# 2.net
KiCad netlist of a schematic drawn in EasyEDA
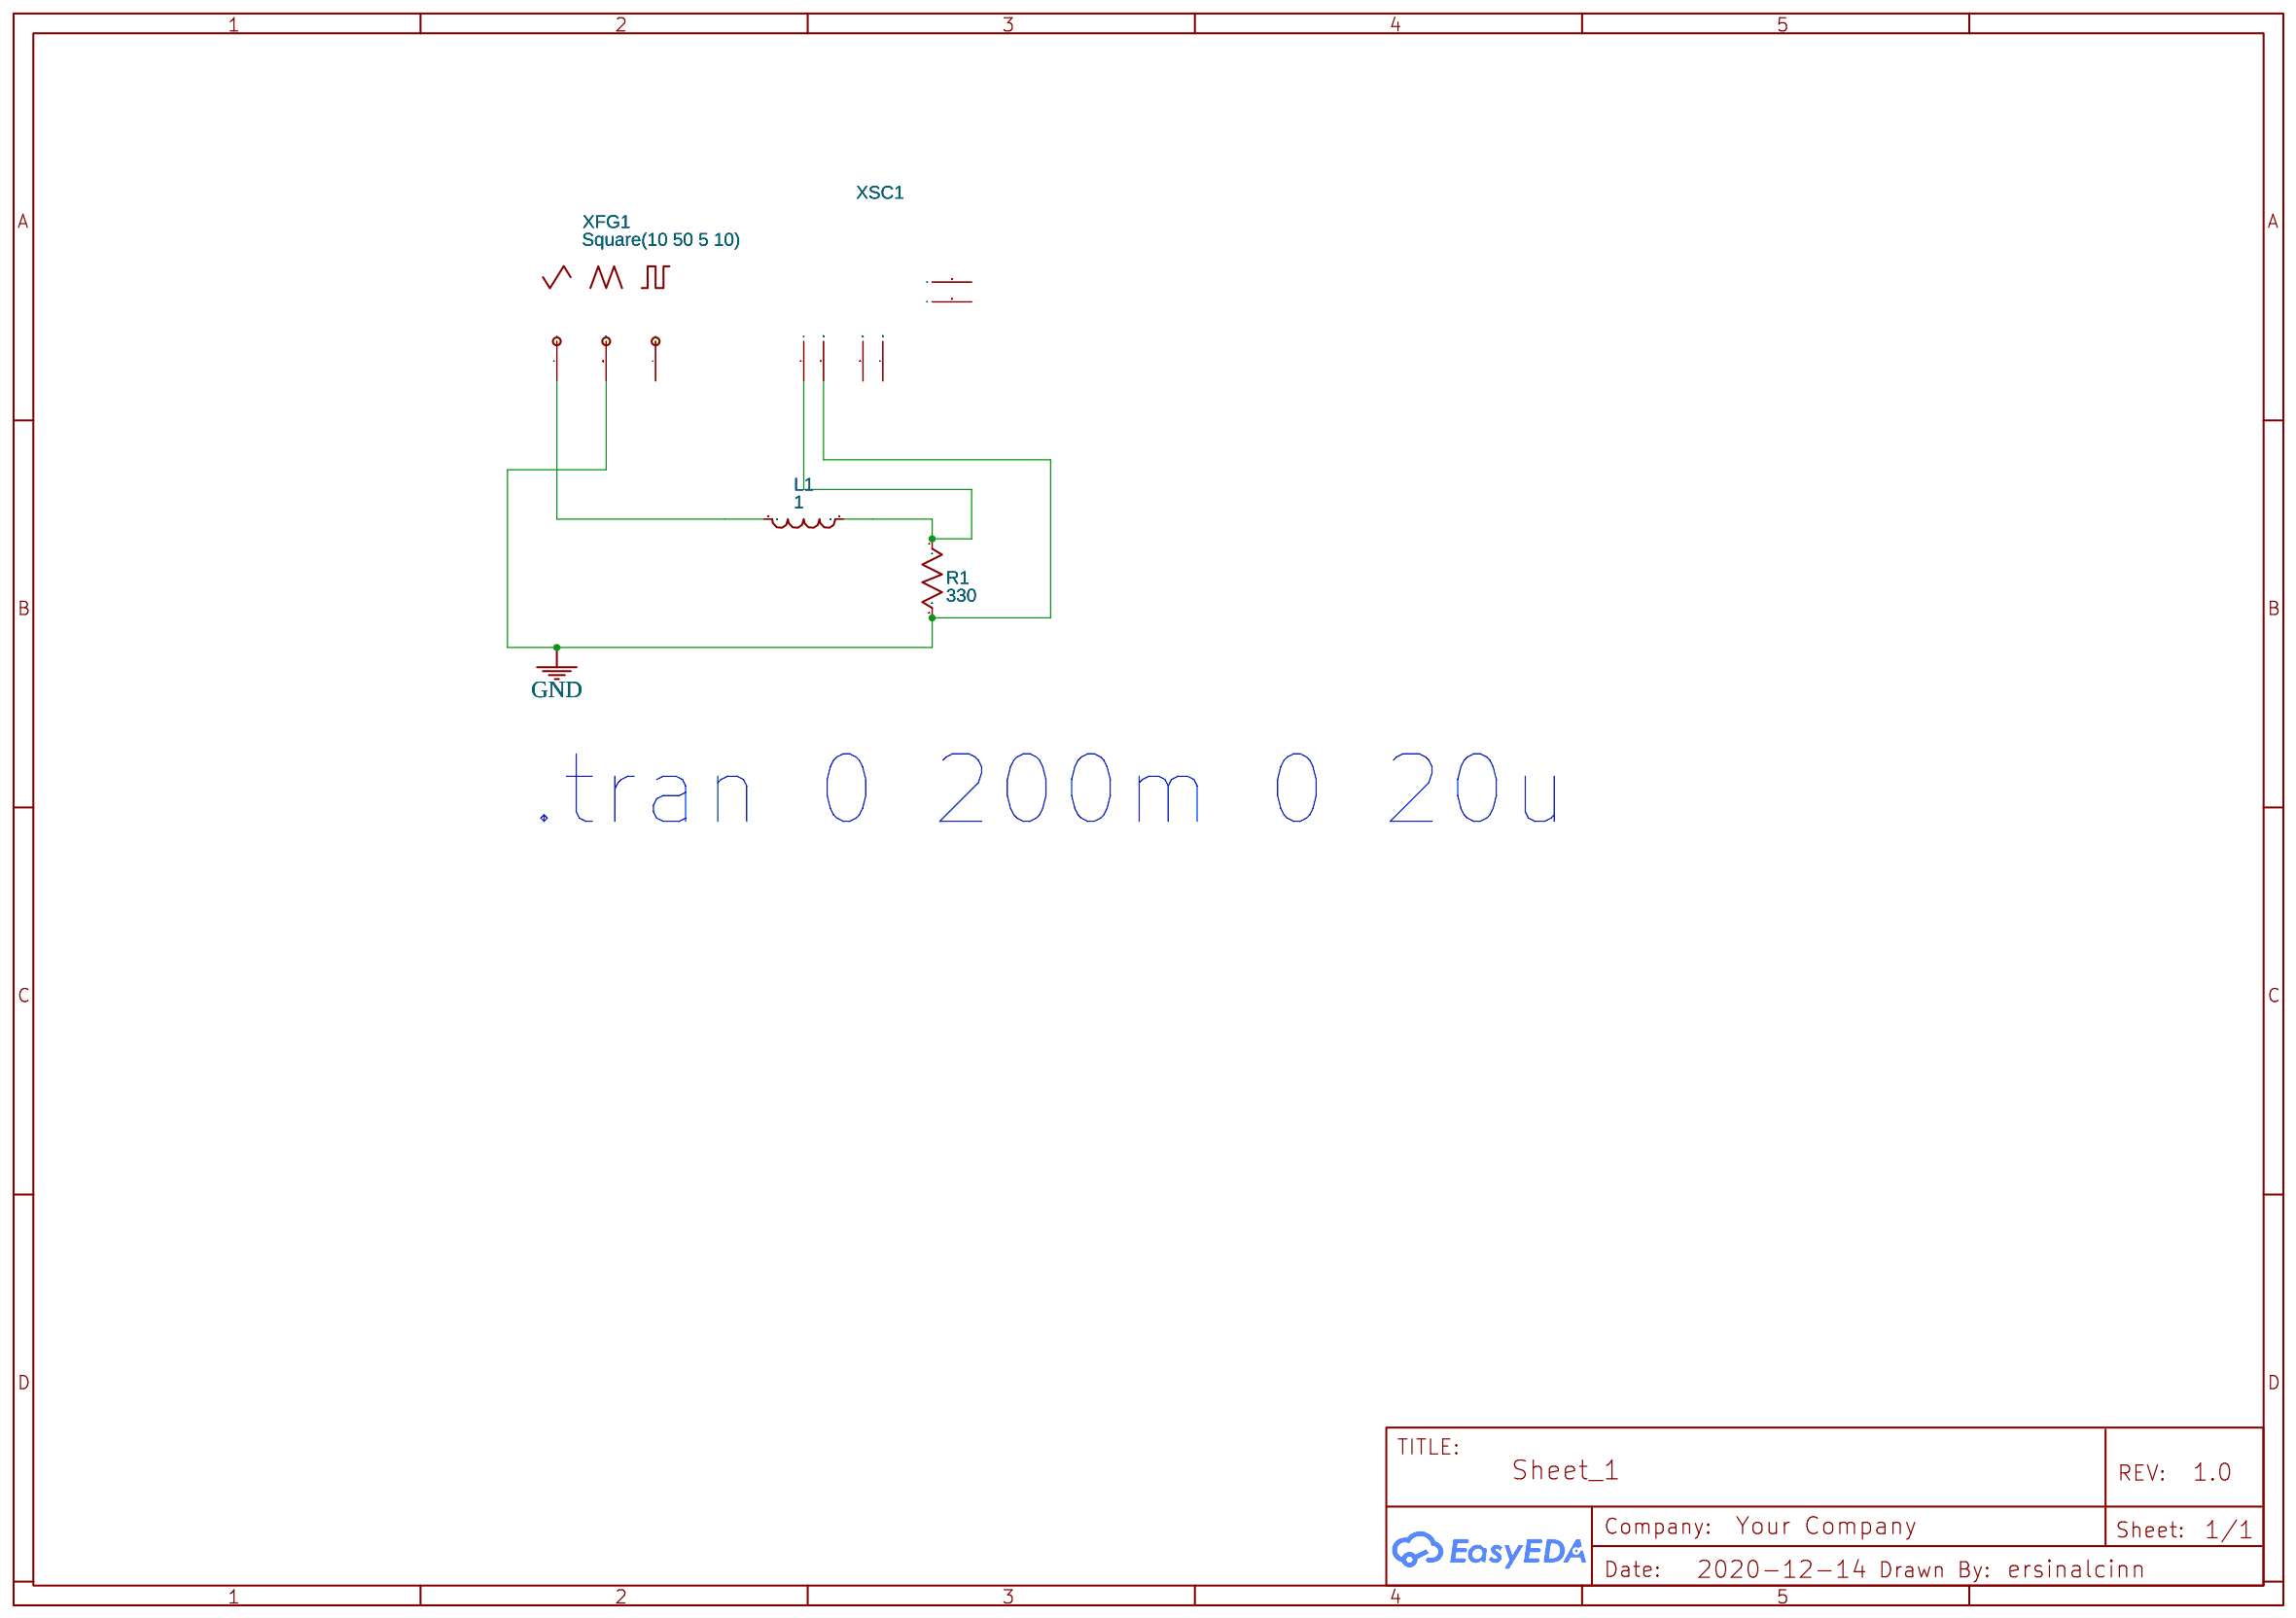
[diagram p0: schematic sheet]

(export (version "E")
  (design (tool "Eeschema 10.0.6"))
  (components
    (comp (ref "L1") (value "1") (libsource (lib "") (part "Inductor")))
    (comp (ref "R1") (value "330") (libsource (lib "") (part "Resistor_US")))
    (comp (ref "XFG1") (value "Square(10 50 5 10)") (libsource (lib "") (part "FUNCTIONGENERATOR")))
    (comp (ref "XSC1") (value "Oscilloscope") (libsource (lib "") (part "OSCILLOSCOPE")))
  )
  (nets
    (net (code "1") (name "GND") (class "Default")
      (node (ref "R1") (pin "2") (pinfunction "2_2") (pintype "unspecified"))
      (node (ref "XFG1") (pin "COM") (pinfunction "COM_COM") (pintype "unspecified"))
      (node (ref "XSC1") (pin "2") (pinfunction "GND1_2") (pintype "unspecified"))
    )
    (net (code "2") (name "Net-(L1-Pad2)") (class "Default")
      (node (ref "L1") (pin "2") (pinfunction "2_2") (pintype "unspecified"))
      (node (ref "XFG1") (pin "+") (pinfunction "+_+") (pintype "unspecified"))
    )
    (net (code "3") (name "Net-(XSC1-A)") (class "Default")
      (node (ref "L1") (pin "1") (pinfunction "1_1") (pintype "unspecified"))
      (node (ref "R1") (pin "1") (pinfunction "1_1") (pintype "unspecified"))
      (node (ref "XSC1") (pin "1") (pinfunction "A_1") (pintype "unspecified"))
    )
    (net (code "4") (name "unconnected-(XFG1-Pad-)") (class "Default")
      (node (ref "XFG1") (pin "-") (pinfunction "-_-") (pintype "unspecified"))
    )
    (net (code "5") (name "unconnected-(XSC1-B-Pad3)") (class "Default")
      (node (ref "XSC1") (pin "3") (pinfunction "B_3") (pintype "unspecified"))
    )
    (net (code "6") (name "unconnected-(XSC1-GND2-Pad4)") (class "Default")
      (node (ref "XSC1") (pin "4") (pinfunction "GND2_4") (pintype "unspecified"))
    )
    (net (code "7") (name "unconnected-(XSC1-T+-Pad5)") (class "Default")
      (node (ref "XSC1") (pin "5") (pinfunction "T+_5") (pintype "unspecified"))
    )
    (net (code "8") (name "unconnected-(XSC1-T--Pad6)") (class "Default")
      (node (ref "XSC1") (pin "6") (pinfunction "T-_6") (pintype "unspecified"))
    )
  )
)
